# BLT_Small_Inflight_PCB_Oct_4.net
KiCad netlist of a schematic drawn in EAGLE
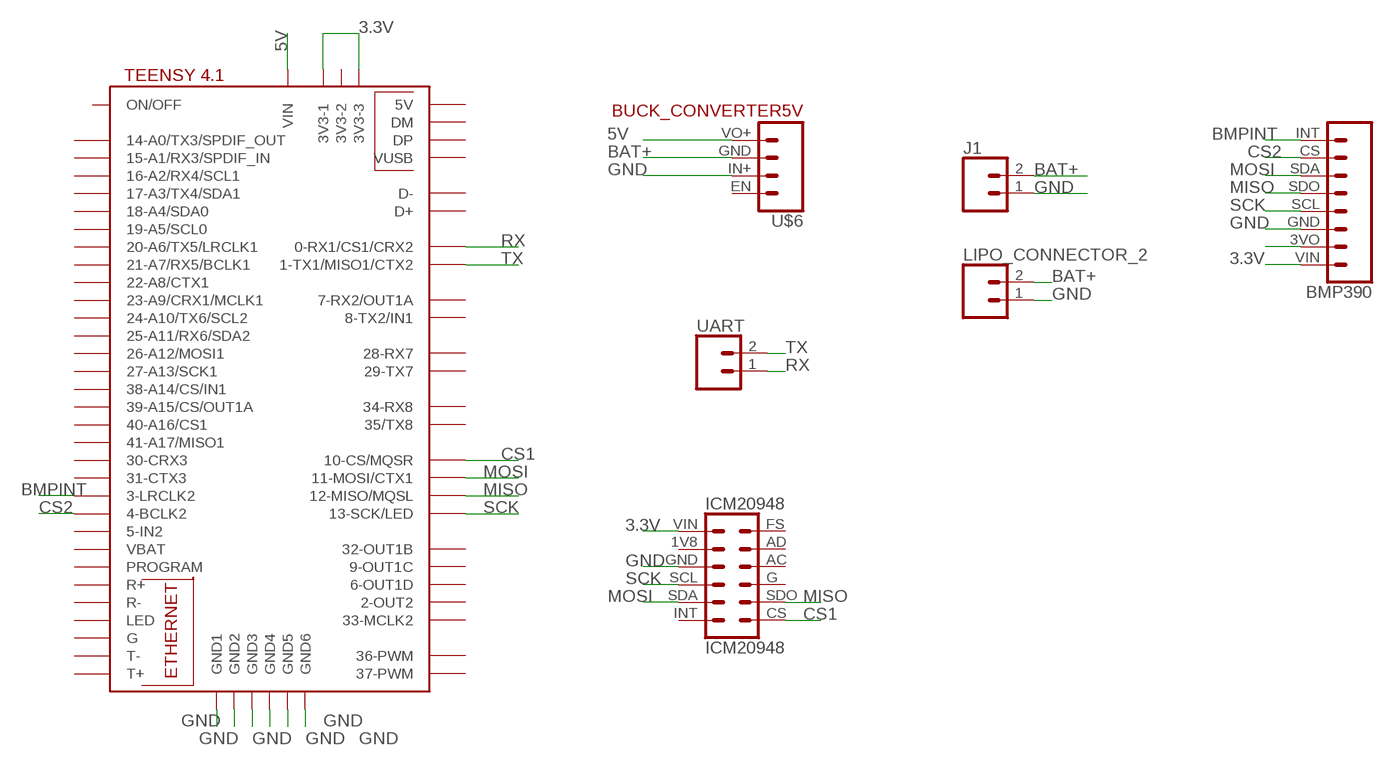
[diagram p0: schematic, sheet 1]

(export (version "E")
  (design (tool "Eeschema 10.0.6"))
  (components
    (comp (ref "J1")
      (value "CONN_02PTH4")
      (footprint "eagle-import:1X02_XTRA_BIG")
      (libsource (lib "eagle-import") (part "CONN_02PTH4"))
    )
    (comp (ref "LIPO_CONNECTOR_2")
      (value "CONN_02")
      (footprint "eagle-import:1X02")
      (libsource (lib "eagle-import") (part "CONN_02"))
    )
    (comp (ref "U$1")
      (value "TEENSY41")
      (footprint "eagle-import:TEENSY41")
      (libsource (lib "eagle-import") (part "TEENSY41"))
    )
    (comp (ref "U$2")
      (value "BMP390")
      (footprint "eagle-import:MICROBUILDER_1X08_ROUND")
      (libsource (lib "eagle-import") (part "BMP390"))
    )
    (comp (ref "U$3")
      (value "ICM20948")
      (footprint "eagle-import:ICM20948")
      (libsource (lib "eagle-import") (part "ICM20948"))
    )
    (comp (ref "U$6")
      (value "BUCK_CONVERTER5V")
      (footprint "eagle-import:1X04")
      (fields (field (name "VOLTAGE") "5V"))
      (libsource (lib "eagle-import") (part "BUCK_CONVERTER5V"))
    )
    (comp (ref "UART")
      (value "CONN_02")
      (footprint "eagle-import:1X02")
      (libsource (lib "eagle-import") (part "CONN_02"))
    )
  )
  (nets
    (net (code "1") (name "/3.3V") (class "Default")
      (node (ref "U$1") (pin "3V3-1") (pinfunction "3V3-1_3V3-1") (pintype "bidirectional"))
      (node (ref "U$1") (pin "3V3-3") (pinfunction "3V3-3_3V3-3") (pintype "bidirectional"))
      (node (ref "U$2") (pin "VIN") (pinfunction "VIN_VIN") (pintype "passive"))
      (node (ref "U$3") (pin "VIN") (pinfunction "VIN_VIN") (pintype "passive"))
    )
    (net (code "2") (name "/5V") (class "Default")
      (node (ref "U$1") (pin "VIN") (pinfunction "VIN_VIN") (pintype "bidirectional"))
      (node (ref "U$6") (pin "VO+") (pinfunction "VO+_VO+") (pintype "passive"))
    )
    (net (code "3") (name "/BAT+") (class "Default")
      (node (ref "J1") (pin "2") (pinfunction "2_2") (pintype "passive"))
      (node (ref "LIPO_CONNECTOR_2") (pin "2") (pinfunction "2_2") (pintype "passive"))
      (node (ref "U$6") (pin "IN+") (pinfunction "IN+_IN+") (pintype "passive"))
    )
    (net (code "4") (name "/BMPINT") (class "Default")
      (node (ref "U$1") (pin "3-LRCLK2") (pinfunction "3-LRCLK2_3-LRCLK2") (pintype "bidirectional"))
      (node (ref "U$2") (pin "INT") (pinfunction "INT_INT") (pintype "passive"))
    )
    (net (code "5") (name "/CS1") (class "Default")
      (node (ref "U$1") (pin "10-CS\\MQSR") (pinfunction "10-CS/MQSR_10-CS\\MQSR") (pintype "bidirectional"))
      (node (ref "U$3") (pin "CS") (pinfunction "CS_CS") (pintype "passive"))
    )
    (net (code "6") (name "/CS2") (class "Default")
      (node (ref "U$1") (pin "4-BCLK2") (pinfunction "4-BCLK2_4-BCLK2") (pintype "bidirectional"))
      (node (ref "U$2") (pin "CS") (pinfunction "CS_CS") (pintype "passive"))
    )
    (net (code "7") (name "/GND") (class "Default")
      (node (ref "J1") (pin "1") (pinfunction "1_1") (pintype "passive"))
      (node (ref "LIPO_CONNECTOR_2") (pin "1") (pinfunction "1_1") (pintype "passive"))
      (node (ref "U$1") (pin "GND1") (pinfunction "GND1_GND1") (pintype "bidirectional"))
      (node (ref "U$1") (pin "GND2") (pinfunction "GND2_GND2") (pintype "bidirectional"))
      (node (ref "U$1") (pin "GND3") (pinfunction "GND3_GND3") (pintype "bidirectional"))
      (node (ref "U$1") (pin "GND4") (pinfunction "GND4_GND4") (pintype "bidirectional"))
      (node (ref "U$1") (pin "GND5") (pinfunction "GND5_GND5") (pintype "bidirectional"))
      (node (ref "U$1") (pin "GND6") (pinfunction "GND6_GND6") (pintype "bidirectional"))
      (node (ref "U$2") (pin "GND") (pinfunction "GND_GND") (pintype "passive"))
      (node (ref "U$3") (pin "GND") (pinfunction "GND_GND") (pintype "passive"))
      (node (ref "U$6") (pin "GND") (pinfunction "GND_GND") (pintype "passive"))
    )
    (net (code "8") (name "/MISO") (class "Default")
      (node (ref "U$1") (pin "12-MISO/MQSL") (pinfunction "12-MISO/MQSL_12-MISO/MQSL") (pintype "bidirectional"))
      (node (ref "U$2") (pin "SDO") (pinfunction "SDO_SDO") (pintype "passive"))
      (node (ref "U$3") (pin "SDO") (pinfunction "SD0_SDO") (pintype "passive"))
    )
    (net (code "9") (name "/MOSI") (class "Default")
      (node (ref "U$1") (pin "11-MOSI/CTX1") (pinfunction "11-MOSI/CTX1_11-MOSI/CTX1") (pintype "bidirectional"))
      (node (ref "U$2") (pin "SDA") (pinfunction "SDA_SDA") (pintype "passive"))
      (node (ref "U$3") (pin "SDA") (pinfunction "SDA_SDA") (pintype "passive"))
    )
    (net (code "10") (name "/RX") (class "Default")
      (node (ref "U$1") (pin "0-RX1/CS1/CRX2") (pinfunction "0-RX1/CS1/CRX2_0-RX1/CS1/CRX2") (pintype "bidirectional"))
      (node (ref "UART") (pin "1") (pinfunction "1_1") (pintype "passive"))
    )
    (net (code "11") (name "/SCK") (class "Default")
      (node (ref "U$1") (pin "13-SCK/LED") (pinfunction "13-SCK/LED_13-SCK/LED") (pintype "bidirectional"))
      (node (ref "U$2") (pin "SCL") (pinfunction "SCL_SCL") (pintype "passive"))
      (node (ref "U$3") (pin "SCL") (pinfunction "SCL_SCL") (pintype "passive"))
    )
    (net (code "12") (name "/TX") (class "Default")
      (node (ref "U$1") (pin "1-TX1/MISO1/CTX2") (pinfunction "1-TX1/MISO1/CTX2_1-TX1/MISO1/CTX2") (pintype "bidirectional"))
      (node (ref "UART") (pin "2") (pinfunction "2_2") (pintype "passive"))
    )
    (net (code "13") (name "unconnected-(U$1-5V-Pad+5V)") (class "Default")
      (node (ref "U$1") (pin "+5V") (pinfunction "5V_+5V") (pintype "bidirectional"))
    )
    (net (code "14") (name "unconnected-(U$1-35{slash}TX8-Pad35-TX8)") (class "Default")
      (node (ref "U$1") (pin "35-TX8") (pinfunction "35/TX8_35-TX8") (pintype "bidirectional"))
    )
    (net (code "15") (name "unconnected-(U$1-Pad2-OUT2)") (class "Default")
      (node (ref "U$1") (pin "2-OUT2") (pinfunction "2-OUT2_2-OUT2") (pintype "bidirectional"))
    )
    (net (code "16") (name "unconnected-(U$1-Pad3V3-2)") (class "Default")
      (node (ref "U$1") (pin "3V3-2") (pinfunction "3V3-2_3V3-2") (pintype "bidirectional"))
    )
    (net (code "17") (name "unconnected-(U$1-Pad5-IN2)") (class "Default")
      (node (ref "U$1") (pin "5-IN2") (pinfunction "5-IN2_5-IN2") (pintype "bidirectional"))
    )
    (net (code "18") (name "unconnected-(U$1-Pad6-OUT1D)") (class "Default")
      (node (ref "U$1") (pin "6-OUT1D") (pinfunction "6-OUT1D_6-OUT1D") (pintype "bidirectional"))
    )
    (net (code "19") (name "unconnected-(U$1-Pad7-RX2{slash}OUT1A)") (class "Default")
      (node (ref "U$1") (pin "7-RX2/OUT1A") (pinfunction "7-RX2/OUT1A_7-RX2/OUT1A") (pintype "bidirectional"))
    )
    (net (code "20") (name "unconnected-(U$1-Pad8-TX2{slash}IN1)") (class "Default")
      (node (ref "U$1") (pin "8-TX2/IN1") (pinfunction "8-TX2/IN1_8-TX2/IN1") (pintype "bidirectional"))
    )
    (net (code "21") (name "unconnected-(U$1-Pad9-OUT1C)") (class "Default")
      (node (ref "U$1") (pin "9-OUT1C") (pinfunction "9-OUT1C_9-OUT1C") (pintype "bidirectional"))
    )
    (net (code "22") (name "unconnected-(U$1-Pad14-A0{slash}TX3{slash}SPDIF_OUT)") (class "Default")
      (node (ref "U$1") (pin "14-A0/TX3/SPDIF_OUT") (pinfunction "14-A0/TX3/SPDIF_OUT_14-A0/TX3/SPDIF_OUT") (pintype "bidirectional"))
    )
    (net (code "23") (name "unconnected-(U$1-Pad15-A1{slash}RX3{slash}SPDIF_IN)") (class "Default")
      (node (ref "U$1") (pin "15-A1/RX3/SPDIF_IN") (pinfunction "15-A1/RX3/SPDIF_IN_15-A1/RX3/SPDIF_IN") (pintype "bidirectional"))
    )
    (net (code "24") (name "unconnected-(U$1-Pad16-A2{slash}RX4{slash}SCL1)") (class "Default")
      (node (ref "U$1") (pin "16-A2/RX4/SCL1") (pinfunction "16-A2/RX4/SCL1_16-A2/RX4/SCL1") (pintype "bidirectional"))
    )
    (net (code "25") (name "unconnected-(U$1-Pad17-A3{slash}TX4{slash}SDA1)") (class "Default")
      (node (ref "U$1") (pin "17-A3/TX4/SDA1") (pinfunction "17-A3/TX4/SDA1_17-A3/TX4/SDA1") (pintype "bidirectional"))
    )
    (net (code "26") (name "unconnected-(U$1-Pad18-A4{slash}SDA0)") (class "Default")
      (node (ref "U$1") (pin "18-A4/SDA0") (pinfunction "18-A4/SDA0_18-A4/SDA0") (pintype "bidirectional"))
    )
    (net (code "27") (name "unconnected-(U$1-Pad19-A5{slash}SCL0)") (class "Default")
      (node (ref "U$1") (pin "19-A5/SCL0") (pinfunction "19-A5/SCL0_19-A5/SCL0") (pintype "bidirectional"))
    )
    (net (code "28") (name "unconnected-(U$1-Pad20-A6{slash}TX5{slash}LRCLK1)") (class "Default")
      (node (ref "U$1") (pin "20-A6/TX5/LRCLK1") (pinfunction "20-A6/TX5/LRCLK1_20-A6/TX5/LRCLK1") (pintype "bidirectional"))
    )
    (net (code "29") (name "unconnected-(U$1-Pad21-A7{slash}RX5{slash}BCLK1)") (class "Default")
      (node (ref "U$1") (pin "21-A7/RX5/BCLK1") (pinfunction "21-A7/RX5/BCLK1_21-A7/RX5/BCLK1") (pintype "bidirectional"))
    )
    (net (code "30") (name "unconnected-(U$1-Pad22-A8{slash}CTX1)") (class "Default")
      (node (ref "U$1") (pin "22-A8/CTX1") (pinfunction "22-A8/CTX1_22-A8/CTX1") (pintype "bidirectional"))
    )
    (net (code "31") (name "unconnected-(U$1-Pad23-A9{slash}CRX1{slash}MCLK1)") (class "Default")
      (node (ref "U$1") (pin "23-A9/CRX1/MCLK1") (pinfunction "23-A9/CRX1/MCLK1_23-A9/CRX1/MCLK1") (pintype "bidirectional"))
    )
    (net (code "32") (name "unconnected-(U$1-Pad24-A10{slash}TX6{slash}SCL2)") (class "Default")
      (node (ref "U$1") (pin "24-A10/TX6/SCL2") (pinfunction "24-A10/TX6/SCL2_24-A10/TX6/SCL2") (pintype "bidirectional"))
    )
    (net (code "33") (name "unconnected-(U$1-Pad25-A11{slash}RX6{slash}SDA2)") (class "Default")
      (node (ref "U$1") (pin "25-A11/RX6/SDA2") (pinfunction "25-A11/RX6/SDA2_25-A11/RX6/SDA2") (pintype "bidirectional"))
    )
    (net (code "34") (name "unconnected-(U$1-Pad26-A12{slash}MOSI1)") (class "Default")
      (node (ref "U$1") (pin "26-A12/MOSI1") (pinfunction "26-A12/MOSI1_26-A12/MOSI1") (pintype "bidirectional"))
    )
    (net (code "35") (name "unconnected-(U$1-Pad27-A13{slash}SCK1)") (class "Default")
      (node (ref "U$1") (pin "27-A13/SCK1") (pinfunction "27-A13/SCK1_27-A13/SCK1") (pintype "bidirectional"))
    )
    (net (code "36") (name "unconnected-(U$1-Pad28-RX7)") (class "Default")
      (node (ref "U$1") (pin "28-RX7") (pinfunction "28-RX7_28-RX7") (pintype "bidirectional"))
    )
    (net (code "37") (name "unconnected-(U$1-Pad29-TX7)") (class "Default")
      (node (ref "U$1") (pin "29-TX7") (pinfunction "29-TX7_29-TX7") (pintype "bidirectional"))
    )
    (net (code "38") (name "unconnected-(U$1-Pad30-CRX3)") (class "Default")
      (node (ref "U$1") (pin "30-CRX3") (pinfunction "30-CRX3_30-CRX3") (pintype "bidirectional"))
    )
    (net (code "39") (name "unconnected-(U$1-Pad31-CTX3)") (class "Default")
      (node (ref "U$1") (pin "31-CTX3") (pinfunction "31-CTX3_31-CTX3") (pintype "bidirectional"))
    )
    (net (code "40") (name "unconnected-(U$1-Pad32-OUT1B)") (class "Default")
      (node (ref "U$1") (pin "32-OUT1B") (pinfunction "32-OUT1B_32-OUT1B") (pintype "bidirectional"))
    )
    (net (code "41") (name "unconnected-(U$1-Pad33-MCLK2)") (class "Default")
      (node (ref "U$1") (pin "33-MCLK2") (pinfunction "33-MCLK2_33-MCLK2") (pintype "bidirectional"))
    )
    (net (code "42") (name "unconnected-(U$1-Pad34-RX8)") (class "Default")
      (node (ref "U$1") (pin "34-RX8") (pinfunction "34-RX8_34-RX8") (pintype "bidirectional"))
    )
    (net (code "43") (name "unconnected-(U$1-Pad36-PWM)") (class "Default")
      (node (ref "U$1") (pin "36-PWM") (pinfunction "36-PWM_36-PWM") (pintype "bidirectional"))
    )
    (net (code "44") (name "unconnected-(U$1-Pad37-PWM)") (class "Default")
      (node (ref "U$1") (pin "37-PWM") (pinfunction "37-PWM_37-PWM") (pintype "bidirectional"))
    )
    (net (code "45") (name "unconnected-(U$1-Pad38-A14{slash}CS{slash}IN1)") (class "Default")
      (node (ref "U$1") (pin "38-A14/CS/IN1") (pinfunction "38-A14/CS/IN1_38-A14/CS/IN1") (pintype "bidirectional"))
    )
    (net (code "46") (name "unconnected-(U$1-Pad39-A15{slash}CS{slash}OUT1A)") (class "Default")
      (node (ref "U$1") (pin "39-A15/CS/OUT1A") (pinfunction "39-A15/CS/OUT1A_39-A15/CS/OUT1A") (pintype "bidirectional"))
    )
    (net (code "47") (name "unconnected-(U$1-Pad40-A16{slash}CS1)") (class "Default")
      (node (ref "U$1") (pin "40-A16/CS1") (pinfunction "40-A16/CS1_40-A16/CS1") (pintype "bidirectional"))
    )
    (net (code "48") (name "unconnected-(U$1-Pad41-A17{slash}MISO1)") (class "Default")
      (node (ref "U$1") (pin "41-A17/MISO1") (pinfunction "41-A17/MISO1_41-A17/MISO1") (pintype "bidirectional"))
    )
    (net (code "49") (name "unconnected-(U$1-PadD+)") (class "Default")
      (node (ref "U$1") (pin "D+") (pinfunction "D+_D+") (pintype "bidirectional"))
    )
    (net (code "50") (name "unconnected-(U$1-PadD-)") (class "Default")
      (node (ref "U$1") (pin "D-") (pinfunction "D-_D-") (pintype "bidirectional"))
    )
    (net (code "51") (name "unconnected-(U$1-PadDM)") (class "Default")
      (node (ref "U$1") (pin "DM") (pinfunction "DM_DM") (pintype "bidirectional"))
    )
    (net (code "52") (name "unconnected-(U$1-PadDP)") (class "Default")
      (node (ref "U$1") (pin "DP") (pinfunction "DP_DP") (pintype "bidirectional"))
    )
    (net (code "53") (name "unconnected-(U$1-PadG)") (class "Default")
      (node (ref "U$1") (pin "G") (pinfunction "G_G") (pintype "bidirectional"))
    )
    (net (code "54") (name "unconnected-(U$1-PadLED)") (class "Default")
      (node (ref "U$1") (pin "LED") (pinfunction "LED_LED") (pintype "bidirectional"))
    )
    (net (code "55") (name "unconnected-(U$1-PadON{slash}OFF)") (class "Default")
      (node (ref "U$1") (pin "ON/OFF") (pinfunction "ON/OFF_ON/OFF") (pintype "bidirectional"))
    )
    (net (code "56") (name "unconnected-(U$1-PadPROGRAM)") (class "Default")
      (node (ref "U$1") (pin "PROGRAM") (pinfunction "PROGRAM_PROGRAM") (pintype "bidirectional"))
    )
    (net (code "57") (name "unconnected-(U$1-PadR+)") (class "Default")
      (node (ref "U$1") (pin "R+") (pinfunction "R+_R+") (pintype "bidirectional"))
    )
    (net (code "58") (name "unconnected-(U$1-PadR-)") (class "Default")
      (node (ref "U$1") (pin "R-") (pinfunction "R-_R-") (pintype "bidirectional"))
    )
    (net (code "59") (name "unconnected-(U$1-PadT+)") (class "Default")
      (node (ref "U$1") (pin "T+") (pinfunction "T+_T+") (pintype "bidirectional"))
    )
    (net (code "60") (name "unconnected-(U$1-PadT-)") (class "Default")
      (node (ref "U$1") (pin "T-") (pinfunction "T-_T-") (pintype "bidirectional"))
    )
    (net (code "61") (name "unconnected-(U$1-PadVBAT)") (class "Default")
      (node (ref "U$1") (pin "VBAT") (pinfunction "VBAT_VBAT") (pintype "bidirectional"))
    )
    (net (code "62") (name "unconnected-(U$1-PadVUSB)") (class "Default")
      (node (ref "U$1") (pin "VUSB") (pinfunction "VUSB_VUSB") (pintype "bidirectional"))
    )
    (net (code "63") (name "unconnected-(U$2-Pad3VO)") (class "Default")
      (node (ref "U$2") (pin "3VO") (pinfunction "3VO_3VO") (pintype "passive"))
    )
    (net (code "64") (name "unconnected-(U$3-Pad1V8)") (class "Default")
      (node (ref "U$3") (pin "1V8") (pinfunction "1V8_1V8") (pintype "passive"))
    )
    (net (code "65") (name "unconnected-(U$3-PadAC)") (class "Default")
      (node (ref "U$3") (pin "AC") (pinfunction "AC_AC") (pintype "passive"))
    )
    (net (code "66") (name "unconnected-(U$3-PadAD)") (class "Default")
      (node (ref "U$3") (pin "AD") (pinfunction "AD_AD") (pintype "passive"))
    )
    (net (code "67") (name "unconnected-(U$3-PadFS)") (class "Default")
      (node (ref "U$3") (pin "FS") (pinfunction "FS_FS") (pintype "passive"))
    )
    (net (code "68") (name "unconnected-(U$3-PadG)") (class "Default")
      (node (ref "U$3") (pin "G") (pinfunction "G_G") (pintype "passive"))
    )
    (net (code "69") (name "unconnected-(U$3-PadINT)") (class "Default")
      (node (ref "U$3") (pin "INT") (pinfunction "INT_INT") (pintype "passive"))
    )
    (net (code "70") (name "unconnected-(U$6-PadEN)") (class "Default")
      (node (ref "U$6") (pin "EN") (pinfunction "EN_EN") (pintype "passive"))
    )
  )
)
